# Board_4_Buttons_WS-TASV__SMD_Plug.net
KiCad netlist of a schematic drawn in EAGLE
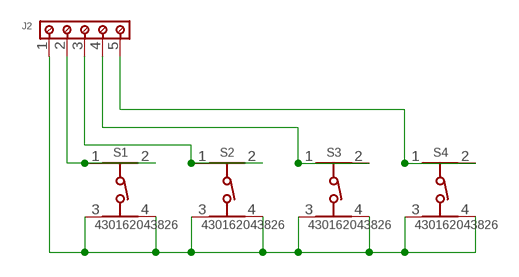
[diagram p0: schematic, sheet 1]

(export (version "E")
  (design (tool "Eeschema 10.0.6"))
  (components
    (comp (ref "J2")
      (value "691709710305")
      (footprint "eagle-import:691709710305")
      (libsource (lib "eagle-import") (part "691709710305"))
    )
    (comp (ref "S1")
      (value "430162043826")
      (footprint "eagle-import:430162043826")
      (libsource (lib "eagle-import") (part "430162043826"))
    )
    (comp (ref "S2")
      (value "430162043826")
      (footprint "eagle-import:430162043826")
      (libsource (lib "eagle-import") (part "430162043826"))
    )
    (comp (ref "S3")
      (value "430162043826")
      (footprint "eagle-import:430162043826")
      (libsource (lib "eagle-import") (part "430162043826"))
    )
    (comp (ref "S4")
      (value "430162043826")
      (footprint "eagle-import:430162043826")
      (libsource (lib "eagle-import") (part "430162043826"))
    )
  )
  (nets
    (net (code "1") (name "Net-(S1-2)") (class "Default")
      (node (ref "J2") (pin "1") (pinfunction "1_1") (pintype "passive"))
      (node (ref "S1") (pin "3") (pinfunction "2_3") (pintype "passive"))
      (node (ref "S1") (pin "4") (pinfunction "4_4") (pintype "passive"))
      (node (ref "S2") (pin "3") (pinfunction "2_3") (pintype "passive"))
      (node (ref "S2") (pin "4") (pinfunction "4_4") (pintype "passive"))
      (node (ref "S3") (pin "3") (pinfunction "2_3") (pintype "passive"))
      (node (ref "S3") (pin "4") (pinfunction "4_4") (pintype "passive"))
      (node (ref "S4") (pin "3") (pinfunction "2_3") (pintype "passive"))
      (node (ref "S4") (pin "4") (pinfunction "4_4") (pintype "passive"))
    )
    (net (code "2") (name "Net-(S1-3)") (class "Default")
      (node (ref "J2") (pin "2") (pinfunction "2_2") (pintype "passive"))
      (node (ref "S1") (pin "1") (pinfunction "1_1") (pintype "passive"))
      (node (ref "S1") (pin "2") (pinfunction "3_2") (pintype "passive"))
    )
    (net (code "3") (name "Net-(S2-3)") (class "Default")
      (node (ref "J2") (pin "3") (pinfunction "3_3") (pintype "passive"))
      (node (ref "S2") (pin "1") (pinfunction "1_1") (pintype "passive"))
      (node (ref "S2") (pin "2") (pinfunction "3_2") (pintype "passive"))
    )
    (net (code "4") (name "Net-(S3-3)") (class "Default")
      (node (ref "J2") (pin "4") (pinfunction "4_4") (pintype "passive"))
      (node (ref "S3") (pin "1") (pinfunction "1_1") (pintype "passive"))
      (node (ref "S3") (pin "2") (pinfunction "3_2") (pintype "passive"))
    )
    (net (code "5") (name "Net-(S4-3)") (class "Default")
      (node (ref "J2") (pin "5") (pinfunction "5_5") (pintype "passive"))
      (node (ref "S4") (pin "1") (pinfunction "1_1") (pintype "passive"))
      (node (ref "S4") (pin "2") (pinfunction "3_2") (pintype "passive"))
    )
  )
)
